# main.net
KiCad netlist of a schematic drawn in EAGLE
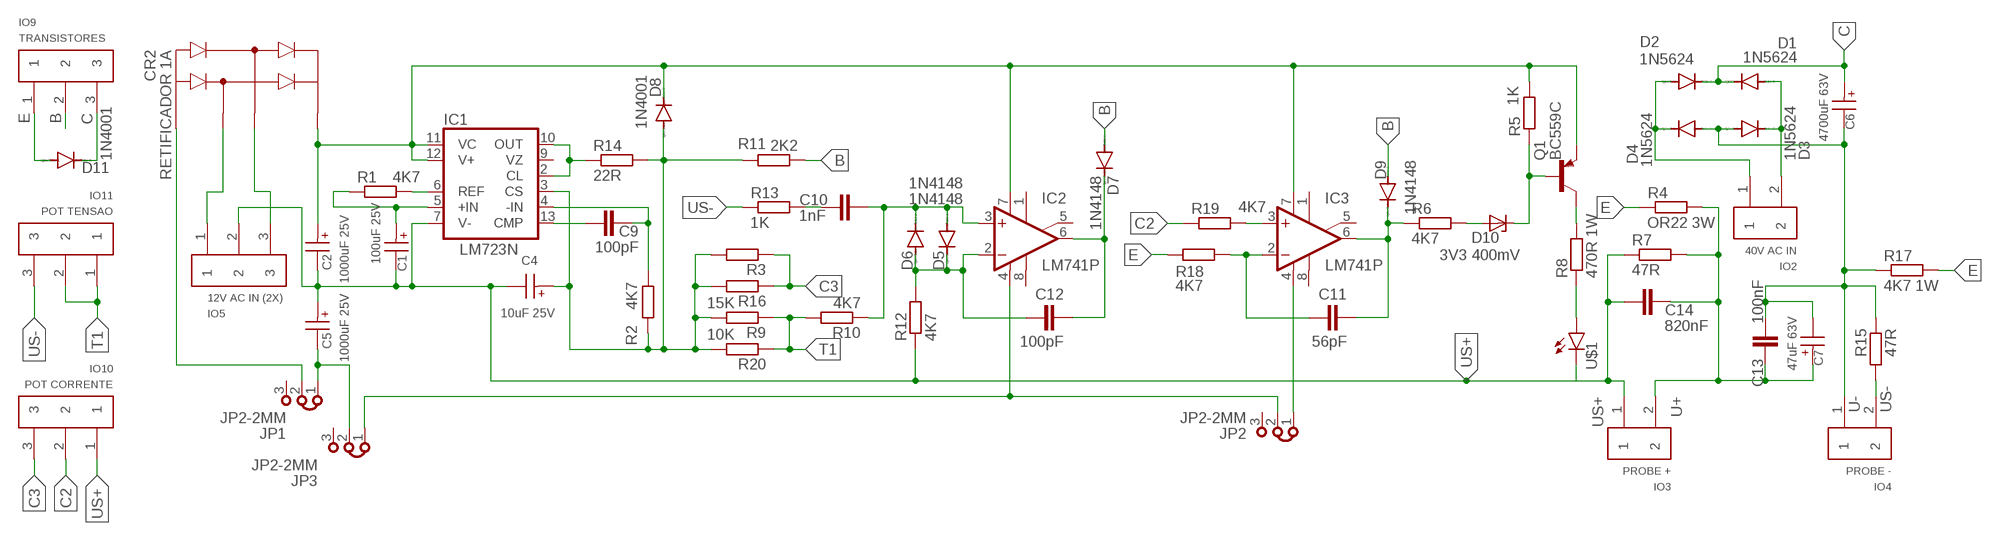
[diagram p0: schematic, sheet 1]

(export (version "E")
  (design (tool "Eeschema 10.0.6"))
  (components
    (comp (ref "C1")
      (value "100uF 25V")
      (footprint "eagle-import:WCAP-ATET_16X31.5(DXL)")
      (libsource (lib "eagle-import") (part "WCAP-ATET_16X31.5_860131280009"))
    )
    (comp (ref "C2")
      (value "1000uF 25V")
      (footprint "eagle-import:WCAP-ATET_16X31.5(DXL)")
      (libsource (lib "eagle-import") (part "WCAP-ATET_16X31.5_860131280009"))
    )
    (comp (ref "C4")
      (value "10uF 25V")
      (footprint "eagle-import:WCAP-ATET_16X31.5(DXL)")
      (libsource (lib "eagle-import") (part "WCAP-ATET_16X31.5_860131280009"))
    )
    (comp (ref "C5")
      (value "1000uF 25V")
      (footprint "eagle-import:WCAP-ATET_16X31.5(DXL)")
      (libsource (lib "eagle-import") (part "WCAP-ATET_16X31.5_860131280009"))
    )
    (comp (ref "C6")
      (value "4700uF 63V")
      (footprint "eagle-import:WCAP-AIG5_35X60(DXL)")
      (libsource (lib "eagle-import") (part "WCAP-AIG5_35X60_861021386035"))
    )
    (comp (ref "C7")
      (value "47uF 63V")
      (footprint "eagle-import:WCAP-AIG5_35X60(DXL)")
      (libsource (lib "eagle-import") (part "WCAP-AIG5_35X60_861021386035"))
    )
    (comp (ref "C9")
      (value "100pF")
      (footprint "eagle-import:C025-025X050")
      (libsource (lib "eagle-import") (part "C-EU025-025X050"))
    )
    (comp (ref "C10")
      (value "1nF")
      (footprint "eagle-import:C025-025X050")
      (libsource (lib "eagle-import") (part "C-EU025-025X050"))
    )
    (comp (ref "C11")
      (value "56pF")
      (footprint "eagle-import:C025-025X050")
      (libsource (lib "eagle-import") (part "C-EU025-025X050"))
    )
    (comp (ref "C12")
      (value "100pF")
      (footprint "eagle-import:C025-025X050")
      (libsource (lib "eagle-import") (part "C-EU025-025X050"))
    )
    (comp (ref "C13")
      (value "100nF")
      (footprint "eagle-import:C025-025X050")
      (libsource (lib "eagle-import") (part "C-EU025-025X050"))
    )
    (comp (ref "C14")
      (value "820nF")
      (footprint "eagle-import:C025-025X050")
      (libsource (lib "eagle-import") (part "C-EU025-025X050"))
    )
    (comp (ref "CR2")
      (value "RETIFICADOR 1A")
      (footprint "eagle-import:THT")
      (fields
        (field (name "DIGIKEY_PARTNO") "KBU8J-E4/51GI-ND")
        (field (name "MANUFACTURER") "Vishay Semiconductor Diodes Division")
        (field (name "MPN") "KBU8J-E4/51")
        (field (name "CREATED_BY") "PCBLayout.com")
      )
      (libsource (lib "eagle-import") (part "KBU8J-E4/51"))
    )
    (comp (ref "D1")
      (value "1N5624")
      (footprint "eagle-import:DO201-15")
      (libsource (lib "eagle-import") (part "1N5624"))
    )
    (comp (ref "D2")
      (value "1N5624")
      (footprint "eagle-import:DO201-15")
      (libsource (lib "eagle-import") (part "1N5624"))
    )
    (comp (ref "D3")
      (value "1N5624")
      (footprint "eagle-import:DO201-15")
      (libsource (lib "eagle-import") (part "1N5624"))
    )
    (comp (ref "D4")
      (value "1N5624")
      (footprint "eagle-import:DO201-15")
      (libsource (lib "eagle-import") (part "1N5624"))
    )
    (comp (ref "D5")
      (value "1N4148")
      (footprint "eagle-import:DO35-7")
      (libsource (lib "eagle-import") (part "1N4148DO35-7"))
    )
    (comp (ref "D6")
      (value "1N4148")
      (footprint "eagle-import:DO35-7")
      (libsource (lib "eagle-import") (part "1N4148DO35-7"))
    )
    (comp (ref "D7")
      (value "1N4148")
      (footprint "eagle-import:DO35-7")
      (libsource (lib "eagle-import") (part "1N4148DO35-7"))
    )
    (comp (ref "D8")
      (value "1N4001")
      (footprint "eagle-import:DO35-7")
      (libsource (lib "eagle-import") (part "1N4148DO35-7"))
    )
    (comp (ref "D9")
      (value "1N4148")
      (footprint "eagle-import:DO35-7")
      (libsource (lib "eagle-import") (part "1N4148DO35-7"))
    )
    (comp (ref "D10")
      (value "3V3 400mV")
      (footprint "eagle-import:DO34Z7")
      (libsource (lib "eagle-import") (part "ZENER-DIODEDO34-7"))
    )
    (comp (ref "D11")
      (value "1N4001")
      (footprint "eagle-import:DO35-7")
      (libsource (lib "eagle-import") (part "1N4148DO35-7"))
    )
    (comp (ref "IC1")
      (value "LM723N")
      (footprint "eagle-import:DIL14")
      (libsource (lib "eagle-import") (part "723NLM"))
    )
    (comp (ref "IC2")
      (value "LM741P")
      (footprint "eagle-import:DIL08")
      (libsource (lib "eagle-import") (part "741PLM"))
    )
    (comp (ref "IC3")
      (value "LM741P")
      (footprint "eagle-import:DIL08")
      (libsource (lib "eagle-import") (part "741PLM"))
    )
    (comp (ref "IO2")
      (value "40V AC IN")
      (footprint "eagle-import:KRE-2P")
      (libsource (lib "eagle-import") (part "KRE-2P"))
    )
    (comp (ref "IO3")
      (value "PROBE +")
      (footprint "eagle-import:KRE-2P")
      (libsource (lib "eagle-import") (part "KRE-2P"))
    )
    (comp (ref "IO4")
      (value "PROBE -")
      (footprint "eagle-import:KRE-2P")
      (libsource (lib "eagle-import") (part "KRE-2P"))
    )
    (comp (ref "IO5")
      (value "12V AC IN (2X)")
      (footprint "eagle-import:KRE-3P")
      (libsource (lib "eagle-import") (part "kre_22383405_KRE-3P"))
    )
    (comp (ref "IO9")
      (value "TRANSISTORES")
      (footprint "eagle-import:KRE-3P")
      (libsource (lib "eagle-import") (part "KRE-3P"))
    )
    (comp (ref "IO10")
      (value "POT CORRENTE")
      (footprint "eagle-import:KRE-3P")
      (libsource (lib "eagle-import") (part "KRE-3P"))
    )
    (comp (ref "IO11")
      (value "POT TENSAO")
      (footprint "eagle-import:KRE-3P")
      (libsource (lib "eagle-import") (part "KRE-3P"))
    )
    (comp (ref "JP1")
      (value "JP2-2MM")
      (footprint "eagle-import:JUMPERS_JP2-2MM")
      (libsource (lib "eagle-import") (part "JUMPERS_JP2-2MM"))
    )
    (comp (ref "JP2")
      (value "JP2-2MM")
      (footprint "eagle-import:JUMPERS_JP2-2MM")
      (libsource (lib "eagle-import") (part "JUMPERS_JP2-2MM"))
    )
    (comp (ref "JP3")
      (value "JP2-2MM")
      (footprint "eagle-import:JUMPERS_JP2-2MM")
      (libsource (lib "eagle-import") (part "JUMPERS_JP2-2MM"))
    )
    (comp (ref "Q1")
      (value "BC559C")
      (footprint "eagle-import:TO92-EBC")
      (libsource (lib "eagle-import") (part "BC559C"))
    )
    (comp (ref "R1")
      (value "4K7")
      (footprint "eagle-import:0204_7")
      (libsource (lib "eagle-import") (part "R-EU_0204/7"))
    )
    (comp (ref "R2")
      (value "4K7")
      (footprint "eagle-import:0204_7")
      (libsource (lib "eagle-import") (part "R-EU_0204/7"))
    )
    (comp (ref "R3")
      (value "R-EU_0204/7")
      (footprint "eagle-import:0204_7")
      (libsource (lib "eagle-import") (part "R-EU_0204/7"))
    )
    (comp (ref "R4")
      (value "OR22 3W")
      (footprint "eagle-import:0204_7")
      (libsource (lib "eagle-import") (part "R-EU_0204/7"))
    )
    (comp (ref "R5")
      (value "1K")
      (footprint "eagle-import:0204_7")
      (libsource (lib "eagle-import") (part "R-EU_0204/7"))
    )
    (comp (ref "R6")
      (value "4K7")
      (footprint "eagle-import:0204_7")
      (libsource (lib "eagle-import") (part "R-EU_0204/7"))
    )
    (comp (ref "R7")
      (value "47R")
      (footprint "eagle-import:0204_7")
      (libsource (lib "eagle-import") (part "R-EU_0204/7"))
    )
    (comp (ref "R8")
      (value "470R 1W")
      (footprint "eagle-import:0204_7")
      (libsource (lib "eagle-import") (part "R-EU_0204/7"))
    )
    (comp (ref "R9")
      (value "10K")
      (footprint "eagle-import:0204_7")
      (libsource (lib "eagle-import") (part "R-EU_0204/7"))
    )
    (comp (ref "R10")
      (value "4K7")
      (footprint "eagle-import:0204_7")
      (libsource (lib "eagle-import") (part "R-EU_0204/7"))
    )
    (comp (ref "R11")
      (value "2K2")
      (footprint "eagle-import:0204_7")
      (libsource (lib "eagle-import") (part "R-EU_0204/7"))
    )
    (comp (ref "R12")
      (value "4K7")
      (footprint "eagle-import:0204_7")
      (libsource (lib "eagle-import") (part "R-EU_0204/7"))
    )
    (comp (ref "R13")
      (value "1K")
      (footprint "eagle-import:0204_7")
      (libsource (lib "eagle-import") (part "R-EU_0204/7"))
    )
    (comp (ref "R14")
      (value "22R")
      (footprint "eagle-import:0204_7")
      (libsource (lib "eagle-import") (part "R-EU_0204/7"))
    )
    (comp (ref "R15")
      (value "47R")
      (footprint "eagle-import:0204_7")
      (libsource (lib "eagle-import") (part "R-EU_0204/7"))
    )
    (comp (ref "R16")
      (value "15K")
      (footprint "eagle-import:0204_7")
      (libsource (lib "eagle-import") (part "R-EU_0204/7"))
    )
    (comp (ref "R17")
      (value "4K7 1W")
      (footprint "eagle-import:0204_7")
      (libsource (lib "eagle-import") (part "R-EU_0204/7"))
    )
    (comp (ref "R18")
      (value "4K7")
      (footprint "eagle-import:0204_7")
      (libsource (lib "eagle-import") (part "R-EU_0204/7"))
    )
    (comp (ref "R19")
      (value "4K7")
      (footprint "eagle-import:0204_7")
      (libsource (lib "eagle-import") (part "R-EU_0204/7"))
    )
    (comp (ref "R20")
      (value "R-EU_0204/7")
      (footprint "eagle-import:0204_7")
      (libsource (lib "eagle-import") (part "R-EU_0204/7"))
    )
    (comp (ref "U$1")
      (value "CLIP")
      (footprint "eagle-import:LED-CIR-5MM-VERMELHO")
      (libsource (lib "eagle-import") (part "LED-CIRCULAR-5MM-VERMELHO"))
    )
  )
  (nets
    (net (code "1") (name "/U+") (class "Default")
      (node (ref "C13") (pin "1") (pinfunction "1_1") (pintype "passive"))
      (node (ref "C14") (pin "1") (pinfunction "1_1") (pintype "passive"))
      (node (ref "C7") (pin "1") (pinfunction "+_1") (pintype "passive"))
      (node (ref "IO3") (pin "2") (pinfunction "2_2") (pintype "bidirectional"))
      (node (ref "R4") (pin "2") (pinfunction "2_2") (pintype "passive"))
      (node (ref "R7") (pin "2") (pinfunction "2_2") (pintype "passive"))
    )
    (net (code "2") (name "/U-") (class "Default")
      (node (ref "C13") (pin "2") (pinfunction "2_2") (pintype "passive"))
      (node (ref "C6") (pin "2") (pinfunction "-_2") (pintype "passive"))
      (node (ref "C7") (pin "2") (pinfunction "-_2") (pintype "passive"))
      (node (ref "D3") (pin "A") (pinfunction "A_A") (pintype "passive"))
      (node (ref "D4") (pin "A") (pinfunction "A_A") (pintype "passive"))
      (node (ref "IO4") (pin "1") (pinfunction "1_1") (pintype "bidirectional"))
      (node (ref "R15") (pin "2") (pinfunction "2_2") (pintype "passive"))
      (node (ref "R17") (pin "1") (pinfunction "1_1") (pintype "passive"))
    )
    (net (code "3") (name "B") (class "Default")
      (node (ref "D7") (pin "A") (pinfunction "A_A") (pintype "passive"))
      (node (ref "D9") (pin "A") (pinfunction "A_A") (pintype "passive"))
      (node (ref "IO9") (pin "2") (pinfunction "2_2") (pintype "bidirectional"))
      (node (ref "R11") (pin "1") (pinfunction "1_1") (pintype "passive"))
    )
    (net (code "4") (name "C") (class "Default")
      (node (ref "C6") (pin "1") (pinfunction "+_1") (pintype "passive"))
      (node (ref "D1") (pin "C") (pinfunction "C_C") (pintype "passive"))
      (node (ref "D11") (pin "C") (pinfunction "C_C") (pintype "passive"))
      (node (ref "D2") (pin "C") (pinfunction "C_C") (pintype "passive"))
      (node (ref "IO9") (pin "3") (pinfunction "3_3") (pintype "bidirectional"))
    )
    (net (code "5") (name "C2") (class "Default")
      (node (ref "IO10") (pin "2") (pinfunction "2_2") (pintype "bidirectional"))
      (node (ref "R19") (pin "1") (pinfunction "1_1") (pintype "passive"))
    )
    (net (code "6") (name "C3") (class "Default")
      (node (ref "IO10") (pin "3") (pinfunction "3_3") (pintype "bidirectional"))
      (node (ref "R16") (pin "1") (pinfunction "1_1") (pintype "passive"))
      (node (ref "R3") (pin "1") (pinfunction "1_1") (pintype "passive"))
    )
    (net (code "7") (name "E") (class "Default")
      (node (ref "D11") (pin "A") (pinfunction "A_A") (pintype "passive"))
      (node (ref "IO9") (pin "1") (pinfunction "1_1") (pintype "bidirectional"))
      (node (ref "R17") (pin "2") (pinfunction "2_2") (pintype "passive"))
      (node (ref "R18") (pin "1") (pinfunction "1_1") (pintype "passive"))
      (node (ref "R4") (pin "1") (pinfunction "1_1") (pintype "passive"))
    )
    (net (code "8") (name "Net-(C1-+)") (class "Default")
      (node (ref "C1") (pin "1") (pinfunction "+_1") (pintype "passive"))
      (node (ref "IC1") (pin "5") (pinfunction "+IN_5") (pintype "input"))
      (node (ref "R1") (pin "1") (pinfunction "1_1") (pintype "passive"))
    )
    (net (code "9") (name "Net-(C2-+)") (class "Default")
      (node (ref "C2") (pin "1") (pinfunction "+_1") (pintype "passive"))
      (node (ref "CR2") (pin "1") (pinfunction "+_1") (pintype "passive"))
      (node (ref "D8") (pin "C") (pinfunction "C_C") (pintype "passive"))
      (node (ref "IC1") (pin "11") (pinfunction "VC_11") (pintype "input"))
      (node (ref "IC1") (pin "12") (pinfunction "V+_12") (pintype "input"))
      (node (ref "IC2") (pin "7") (pinfunction "V+_7") (pintype "power_in"))
      (node (ref "IC3") (pin "7") (pinfunction "V+_7") (pintype "power_in"))
      (node (ref "Q1") (pin "E") (pinfunction "E_E") (pintype "passive"))
      (node (ref "R5") (pin "2") (pinfunction "2_2") (pintype "passive"))
    )
    (net (code "10") (name "Net-(C4-+)") (class "Default")
      (node (ref "C4") (pin "1") (pinfunction "+_1") (pintype "passive"))
      (node (ref "D8") (pin "A") (pinfunction "A_A") (pintype "passive"))
      (node (ref "IC1") (pin "3") (pinfunction "CS_3") (pintype "input"))
      (node (ref "R11") (pin "2") (pinfunction "2_2") (pintype "passive"))
      (node (ref "R14") (pin "2") (pinfunction "2_2") (pintype "passive"))
      (node (ref "R16") (pin "2") (pinfunction "2_2") (pintype "passive"))
      (node (ref "R2") (pin "1") (pinfunction "1_1") (pintype "passive"))
      (node (ref "R20") (pin "2") (pinfunction "2_2") (pintype "passive"))
      (node (ref "R3") (pin "2") (pinfunction "2_2") (pintype "passive"))
      (node (ref "R9") (pin "2") (pinfunction "2_2") (pintype "passive"))
    )
    (net (code "11") (name "Net-(C5--)") (class "Default")
      (node (ref "C5") (pin "2") (pinfunction "-_2") (pintype "passive"))
      (node (ref "JP1") (pin "1") (pinfunction "1_1") (pintype "passive"))
      (node (ref "JP3") (pin "2") (pinfunction "2_2") (pintype "passive"))
    )
    (net (code "12") (name "Net-(C10-Pad2)") (class "Default")
      (node (ref "C10") (pin "2") (pinfunction "2_2") (pintype "passive"))
      (node (ref "R13") (pin "2") (pinfunction "2_2") (pintype "passive"))
    )
    (net (code "13") (name "Net-(CR2--)") (class "Default")
      (node (ref "CR2") (pin "4") (pinfunction "-_4") (pintype "passive"))
      (node (ref "JP1") (pin "2") (pinfunction "2_2") (pintype "passive"))
    )
    (net (code "14") (name "Net-(CR2-~)") (class "Default")
      (node (ref "CR2") (pin "2") (pinfunction "~_2") (pintype "passive"))
      (node (ref "IO5") (pin "1") (pinfunction "1_1") (pintype "bidirectional"))
    )
    (net (code "15") (name "Net-(CR2-~{_1})") (class "Default")
      (node (ref "CR2") (pin "3") (pinfunction "~{_1}_3") (pintype "passive"))
      (node (ref "IO5") (pin "3") (pinfunction "3_3") (pintype "bidirectional"))
    )
    (net (code "16") (name "Net-(D1-PadA)") (class "Default")
      (node (ref "D1") (pin "A") (pinfunction "A_A") (pintype "passive"))
      (node (ref "D3") (pin "C") (pinfunction "C_C") (pintype "passive"))
      (node (ref "IO2") (pin "2") (pinfunction "2_2") (pintype "bidirectional"))
    )
    (net (code "17") (name "Net-(D2-PadA)") (class "Default")
      (node (ref "D2") (pin "A") (pinfunction "A_A") (pintype "passive"))
      (node (ref "D4") (pin "C") (pinfunction "C_C") (pintype "passive"))
      (node (ref "IO2") (pin "1") (pinfunction "1_1") (pintype "bidirectional"))
    )
    (net (code "18") (name "Net-(D10-PadA)") (class "Default")
      (node (ref "D10") (pin "A") (pinfunction "A_A") (pintype "passive"))
      (node (ref "R6") (pin "2") (pinfunction "2_2") (pintype "passive"))
    )
    (net (code "19") (name "Net-(D10-PadC)") (class "Default")
      (node (ref "D10") (pin "C") (pinfunction "C_C") (pintype "passive"))
      (node (ref "Q1") (pin "B") (pinfunction "B_B") (pintype "passive"))
      (node (ref "R5") (pin "1") (pinfunction "1_1") (pintype "passive"))
    )
    (net (code "20") (name "Net-(IC1--IN)") (class "Default")
      (node (ref "C9") (pin "2") (pinfunction "2_2") (pintype "passive"))
      (node (ref "IC1") (pin "4") (pinfunction "-IN_4") (pintype "input"))
      (node (ref "R2") (pin "2") (pinfunction "2_2") (pintype "passive"))
    )
    (net (code "21") (name "Net-(IC1-CL)") (class "Default")
      (node (ref "IC1") (pin "10") (pinfunction "OUT_10") (pintype "output"))
      (node (ref "IC1") (pin "2") (pinfunction "CL_2") (pintype "input"))
      (node (ref "R14") (pin "1") (pinfunction "1_1") (pintype "passive"))
    )
    (net (code "22") (name "Net-(IC1-CMP)") (class "Default")
      (node (ref "C9") (pin "1") (pinfunction "1_1") (pintype "passive"))
      (node (ref "IC1") (pin "13") (pinfunction "CMP_13") (pintype "passive"))
    )
    (net (code "23") (name "Net-(IC1-REF)") (class "Default")
      (node (ref "IC1") (pin "6") (pinfunction "REF_6") (pintype "output"))
      (node (ref "R1") (pin "2") (pinfunction "2_2") (pintype "passive"))
    )
    (net (code "24") (name "Net-(IC2-+IN)") (class "Default")
      (node (ref "C10") (pin "1") (pinfunction "1_1") (pintype "passive"))
      (node (ref "D5") (pin "A") (pinfunction "A_A") (pintype "passive"))
      (node (ref "D6") (pin "C") (pinfunction "C_C") (pintype "passive"))
      (node (ref "IC2") (pin "3") (pinfunction "+IN_3") (pintype "input"))
      (node (ref "R10") (pin "1") (pinfunction "1_1") (pintype "passive"))
    )
    (net (code "25") (name "Net-(IC2--IN)") (class "Default")
      (node (ref "C12") (pin "1") (pinfunction "1_1") (pintype "passive"))
      (node (ref "D5") (pin "C") (pinfunction "C_C") (pintype "passive"))
      (node (ref "D6") (pin "A") (pinfunction "A_A") (pintype "passive"))
      (node (ref "IC2") (pin "2") (pinfunction "-IN_2") (pintype "input"))
      (node (ref "R12") (pin "2") (pinfunction "2_2") (pintype "passive"))
    )
    (net (code "26") (name "Net-(IC2-OUT)") (class "Default")
      (node (ref "C12") (pin "2") (pinfunction "2_2") (pintype "passive"))
      (node (ref "D7") (pin "C") (pinfunction "C_C") (pintype "passive"))
      (node (ref "IC2") (pin "6") (pinfunction "OUT_6") (pintype "output"))
    )
    (net (code "27") (name "Net-(IC2-V-)") (class "Default")
      (node (ref "IC2") (pin "4") (pinfunction "V-_4") (pintype "power_in"))
      (node (ref "JP2") (pin "2") (pinfunction "2_2") (pintype "passive"))
      (node (ref "JP3") (pin "1") (pinfunction "1_1") (pintype "passive"))
    )
    (net (code "28") (name "Net-(IC3-+IN)") (class "Default")
      (node (ref "IC3") (pin "3") (pinfunction "+IN_3") (pintype "input"))
      (node (ref "R19") (pin "2") (pinfunction "2_2") (pintype "passive"))
    )
    (net (code "29") (name "Net-(IC3--IN)") (class "Default")
      (node (ref "C11") (pin "1") (pinfunction "1_1") (pintype "passive"))
      (node (ref "IC3") (pin "2") (pinfunction "-IN_2") (pintype "input"))
      (node (ref "R18") (pin "2") (pinfunction "2_2") (pintype "passive"))
    )
    (net (code "30") (name "Net-(IC3-OUT)") (class "Default")
      (node (ref "C11") (pin "2") (pinfunction "2_2") (pintype "passive"))
      (node (ref "D9") (pin "C") (pinfunction "C_C") (pintype "passive"))
      (node (ref "IC3") (pin "6") (pinfunction "OUT_6") (pintype "output"))
      (node (ref "R6") (pin "1") (pinfunction "1_1") (pintype "passive"))
    )
    (net (code "31") (name "Net-(IC3-V-)") (class "Default")
      (node (ref "IC3") (pin "4") (pinfunction "V-_4") (pintype "power_in"))
      (node (ref "JP2") (pin "1") (pinfunction "1_1") (pintype "passive"))
    )
    (net (code "32") (name "Net-(Q1-PadC)") (class "Default")
      (node (ref "Q1") (pin "C") (pinfunction "C_C") (pintype "passive"))
      (node (ref "R8") (pin "2") (pinfunction "2_2") (pintype "passive"))
    )
    (net (code "33") (name "Net-(U$1-ANODE)") (class "Default")
      (node (ref "R8") (pin "1") (pinfunction "1_1") (pintype "passive"))
      (node (ref "U$1") (pin "A") (pinfunction "ANODE_A") (pintype "passive"))
    )
    (net (code "34") (name "T1") (class "Default")
      (node (ref "IO11") (pin "1") (pinfunction "1_1") (pintype "bidirectional"))
      (node (ref "IO11") (pin "2") (pinfunction "2_2") (pintype "bidirectional"))
      (node (ref "R10") (pin "2") (pinfunction "2_2") (pintype "passive"))
      (node (ref "R20") (pin "1") (pinfunction "1_1") (pintype "passive"))
      (node (ref "R9") (pin "1") (pinfunction "1_1") (pintype "passive"))
    )
    (net (code "35") (name "US+") (class "Default")
      (node (ref "C1") (pin "2") (pinfunction "-_2") (pintype "passive"))
      (node (ref "C14") (pin "2") (pinfunction "2_2") (pintype "passive"))
      (node (ref "C2") (pin "2") (pinfunction "-_2") (pintype "passive"))
      (node (ref "C4") (pin "2") (pinfunction "-_2") (pintype "passive"))
      (node (ref "C5") (pin "1") (pinfunction "+_1") (pintype "passive"))
      (node (ref "IC1") (pin "7") (pinfunction "V-_7") (pintype "input"))
      (node (ref "IO10") (pin "1") (pinfunction "1_1") (pintype "bidirectional"))
      (node (ref "IO3") (pin "1") (pinfunction "1_1") (pintype "bidirectional"))
      (node (ref "IO5") (pin "2") (pinfunction "2_2") (pintype "bidirectional"))
      (node (ref "R12") (pin "1") (pinfunction "1_1") (pintype "passive"))
      (node (ref "R7") (pin "1") (pinfunction "1_1") (pintype "passive"))
      (node (ref "U$1") (pin "K") (pinfunction "CATHODE_K") (pintype "passive"))
    )
    (net (code "36") (name "US-") (class "Default")
      (node (ref "IO11") (pin "3") (pinfunction "3_3") (pintype "bidirectional"))
      (node (ref "IO4") (pin "2") (pinfunction "2_2") (pintype "bidirectional"))
      (node (ref "R13") (pin "1") (pinfunction "1_1") (pintype "passive"))
      (node (ref "R15") (pin "1") (pinfunction "1_1") (pintype "passive"))
    )
    (net (code "37") (name "unconnected-(IC1-VZ-Pad9)") (class "Default")
      (node (ref "IC1") (pin "9") (pinfunction "VZ_9") (pintype "output"))
    )
    (net (code "38") (name "unconnected-(IC2-ON1-Pad1)") (class "Default")
      (node (ref "IC2") (pin "1") (pinfunction "ON1_1") (pintype "passive"))
    )
    (net (code "39") (name "unconnected-(IC2-ON2-Pad5)") (class "Default")
      (node (ref "IC2") (pin "5") (pinfunction "ON2_5") (pintype "passive"))
    )
    (net (code "40") (name "unconnected-(IC2-OPT-Pad8)") (class "Default")
      (node (ref "IC2") (pin "8") (pinfunction "OPT_8") (pintype "passive"))
    )
    (net (code "41") (name "unconnected-(IC3-ON1-Pad1)") (class "Default")
      (node (ref "IC3") (pin "1") (pinfunction "ON1_1") (pintype "passive"))
    )
    (net (code "42") (name "unconnected-(IC3-ON2-Pad5)") (class "Default")
      (node (ref "IC3") (pin "5") (pinfunction "ON2_5") (pintype "passive"))
    )
    (net (code "43") (name "unconnected-(IC3-OPT-Pad8)") (class "Default")
      (node (ref "IC3") (pin "8") (pinfunction "OPT_8") (pintype "passive"))
    )
    (net (code "44") (name "unconnected-(JP1-Pad3)") (class "Default")
      (node (ref "JP1") (pin "3") (pinfunction "3_3") (pintype "passive"))
    )
    (net (code "45") (name "unconnected-(JP2-Pad3)") (class "Default")
      (node (ref "JP2") (pin "3") (pinfunction "3_3") (pintype "passive"))
    )
    (net (code "46") (name "unconnected-(JP3-Pad3)") (class "Default")
      (node (ref "JP3") (pin "3") (pinfunction "3_3") (pintype "passive"))
    )
  )
)
